# USB-Isolator_v10.net
KiCad netlist of a schematic drawn in EAGLE
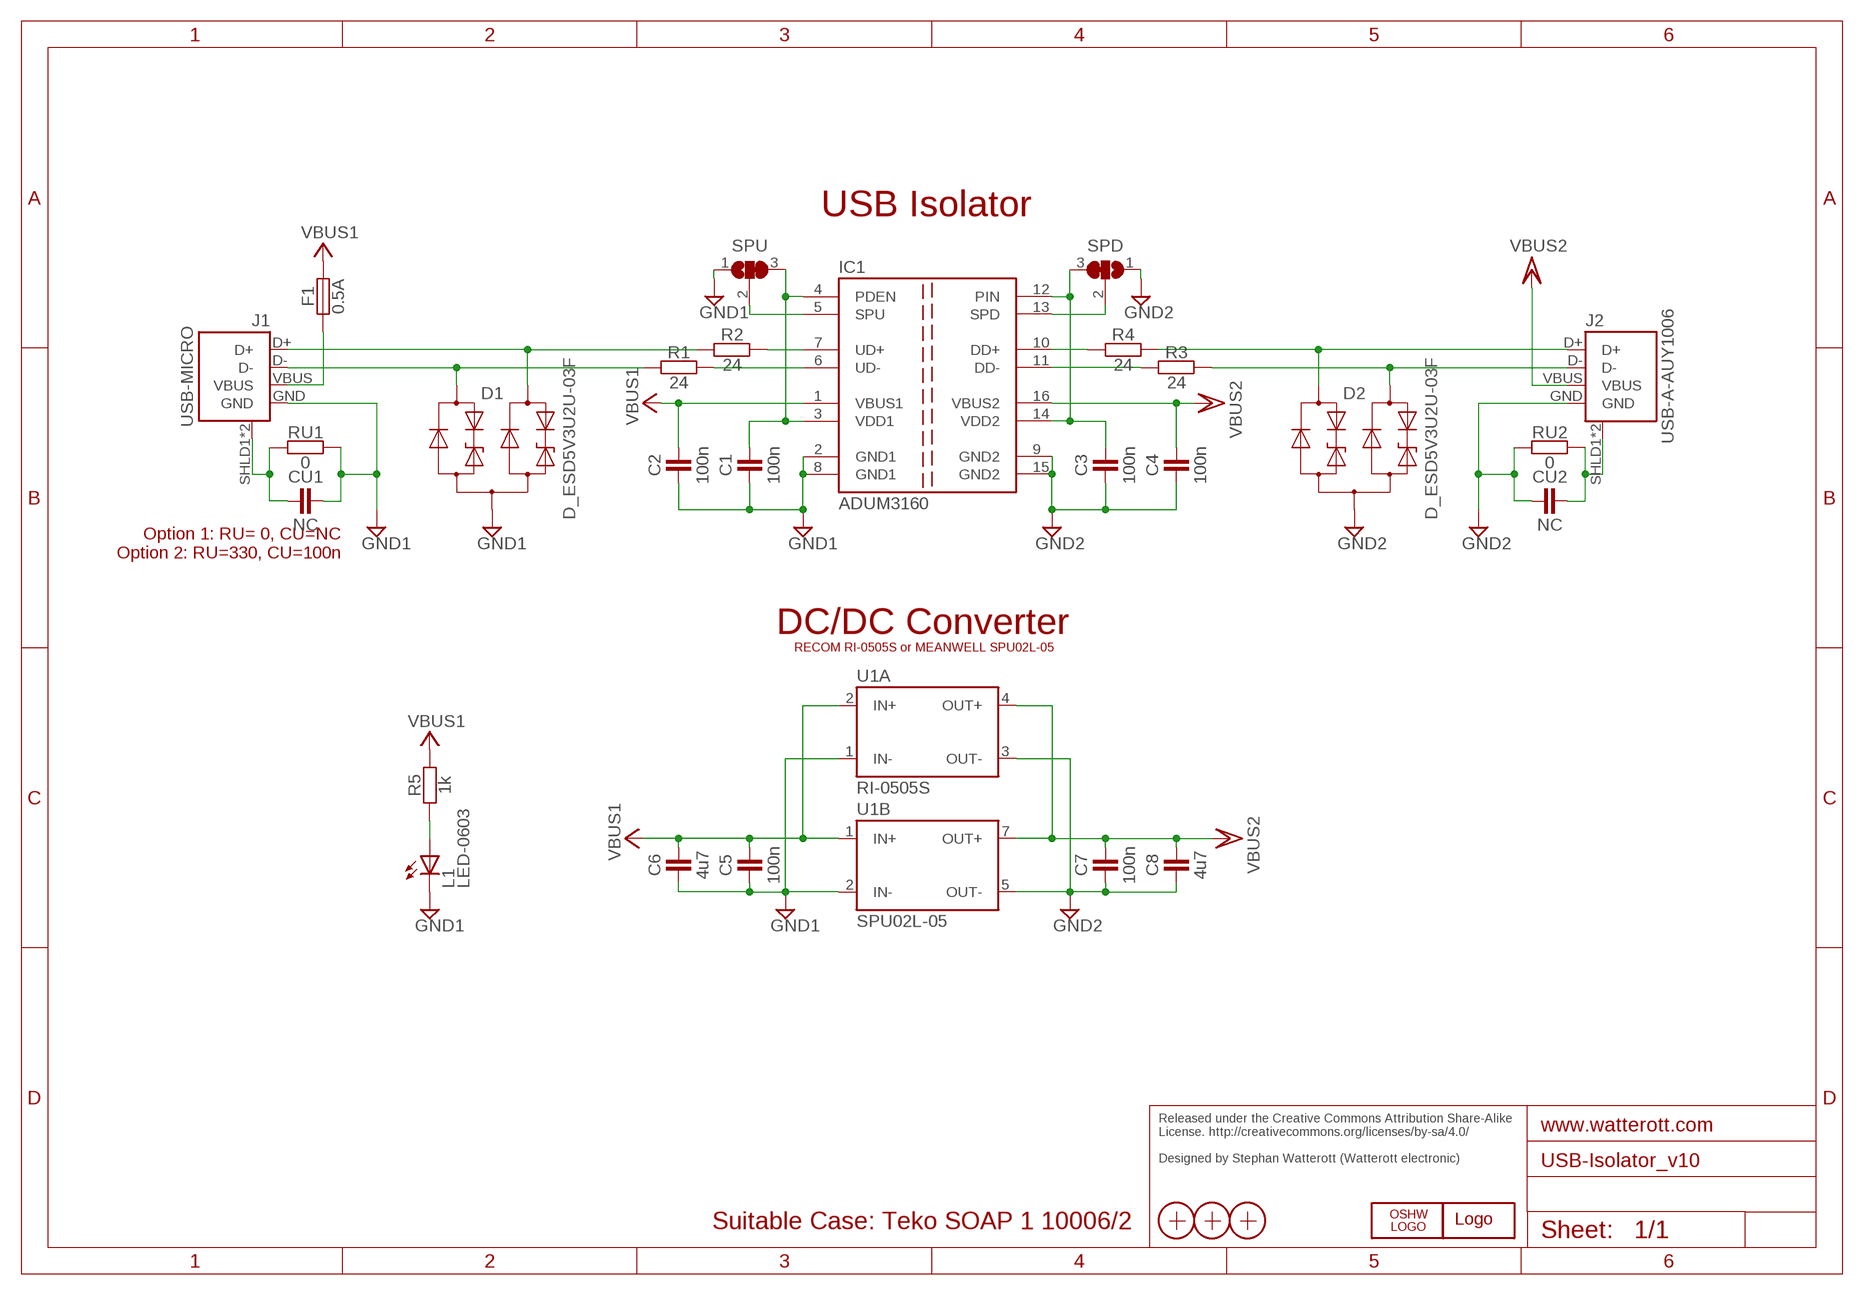
[diagram p0: schematic, sheet 1]

(export (version "E")
  (design (tool "Eeschema 10.0.6"))
  (components
    (comp (ref "C1")
      (value "100n")
      (footprint "eagle-import:R0603")
      (libsource (lib "eagle-import") (part "CAPACITOR-C0603"))
    )
    (comp (ref "C2")
      (value "100n")
      (footprint "eagle-import:R0603")
      (libsource (lib "eagle-import") (part "CAPACITOR-C0603"))
    )
    (comp (ref "C3")
      (value "100n")
      (footprint "eagle-import:R0603")
      (libsource (lib "eagle-import") (part "CAPACITOR-C0603"))
    )
    (comp (ref "C4")
      (value "100n")
      (footprint "eagle-import:R0603")
      (libsource (lib "eagle-import") (part "CAPACITOR-C0603"))
    )
    (comp (ref "C5")
      (value "100n")
      (footprint "eagle-import:R0603")
      (libsource (lib "eagle-import") (part "CAPACITOR-C0603"))
    )
    (comp (ref "C6")
      (value "4u7")
      (footprint "eagle-import:R1206")
      (libsource (lib "eagle-import") (part "CAPACITOR-C1206"))
    )
    (comp (ref "C7")
      (value "100n")
      (footprint "eagle-import:R0603")
      (libsource (lib "eagle-import") (part "CAPACITOR-C0603"))
    )
    (comp (ref "C8")
      (value "4u7")
      (footprint "eagle-import:R1206")
      (libsource (lib "eagle-import") (part "CAPACITOR-C1206"))
    )
    (comp (ref "CU1")
      (value "NC")
      (footprint "eagle-import:R0603")
      (libsource (lib "eagle-import") (part "CAPACITOR-C0603"))
    )
    (comp (ref "CU2")
      (value "NC")
      (footprint "eagle-import:R0603")
      (libsource (lib "eagle-import") (part "CAPACITOR-C0603"))
    )
    (comp (ref "D1")
      (value "D_ESD5V3U2U-03F")
      (footprint "eagle-import:TSFP3")
      (libsource (lib "eagle-import") (part "D_ESD5V3U2U-03F"))
    )
    (comp (ref "D2")
      (value "D_ESD5V3U2U-03F")
      (footprint "eagle-import:TSFP3")
      (libsource (lib "eagle-import") (part "D_ESD5V3U2U-03F"))
    )
    (comp (ref "F1")
      (value "0.5A")
      (footprint "eagle-import:R0805")
      (libsource (lib "eagle-import") (part "FUSE-0805"))
    )
    (comp (ref "IC1")
      (value "ADUM3160")
      (footprint "eagle-import:SO16W")
      (libsource (lib "eagle-import") (part "ADUM3160"))
    )
    (comp (ref "J1")
      (value "USB-MICRO")
      (footprint "eagle-import:USB-MICRO-10103594")
      (libsource (lib "eagle-import") (part "USB-MICRO"))
    )
    (comp (ref "J2")
      (value "USB-A-AUY1006")
      (footprint "eagle-import:USB-AU-Y1006-R")
      (fields (field (name "MANUFACTURER") "AU-Y1006-R"))
      (libsource (lib "eagle-import") (part "USB-A-AUY1006"))
    )
    (comp (ref "L1")
      (value "LED-0603")
      (footprint "eagle-import:LED_0603")
      (libsource (lib "eagle-import") (part "LED-0603"))
    )
    (comp (ref "LOGO2")
      (value "OSHW_LOGOX0070")
      (footprint "eagle-import:OSHW_6X70")
      (libsource (lib "eagle-import") (part "OSHW_LOGOX0070"))
    )
    (comp (ref "LOGO3")
      (value "LOGO-S_PLACE_M")
      (footprint "eagle-import:SPARK_TPLACE_M")
      (libsource (lib "eagle-import") (part "LOGO-S_PLACE_M"))
    )
    (comp (ref "R1")
      (value "24")
      (footprint "eagle-import:R0603")
      (libsource (lib "eagle-import") (part "RESISTOR-R0603"))
    )
    (comp (ref "R2")
      (value "24")
      (footprint "eagle-import:R0603")
      (libsource (lib "eagle-import") (part "RESISTOR-R0603"))
    )
    (comp (ref "R3")
      (value "24")
      (footprint "eagle-import:R0603")
      (libsource (lib "eagle-import") (part "RESISTOR-R0603"))
    )
    (comp (ref "R4")
      (value "24")
      (footprint "eagle-import:R0603")
      (libsource (lib "eagle-import") (part "RESISTOR-R0603"))
    )
    (comp (ref "R5")
      (value "1k")
      (footprint "eagle-import:R0603")
      (libsource (lib "eagle-import") (part "RESISTOR-R0603"))
    )
    (comp (ref "RU1")
      (value "0")
      (footprint "eagle-import:R0603")
      (libsource (lib "eagle-import") (part "RESISTOR-R0603"))
    )
    (comp (ref "RU2")
      (value "0")
      (footprint "eagle-import:R0603")
      (libsource (lib "eagle-import") (part "RESISTOR-R0603"))
    )
    (comp (ref "SPD")
      (value "JUMPER3")
      (footprint "eagle-import:JUMPER3")
      (libsource (lib "eagle-import") (part "JUMPER3"))
    )
    (comp (ref "SPU")
      (value "JUMPER3")
      (footprint "eagle-import:JUMPER3")
      (libsource (lib "eagle-import") (part "JUMPER3"))
    )
    (comp (ref "U1A")
      (value "RI-0505S")
      (footprint "eagle-import:RECOM_SIP4_RI")
      (libsource (lib "eagle-import") (part "DC/DC-RI"))
    )
    (comp (ref "U1B")
      (value "SPU02L-05")
      (footprint "eagle-import:MEANWELL_SIP7_SPU02")
      (libsource (lib "eagle-import") (part "DC/DC-SPU02"))
    )
    (comp (ref "X1")
      (value "PASSER-07")
      (footprint "eagle-import:PASSER_07MM")
      (libsource (lib "eagle-import") (part "PASSER-07"))
    )
    (comp (ref "X2")
      (value "PASSER-07")
      (footprint "eagle-import:PASSER_07MM")
      (libsource (lib "eagle-import") (part "PASSER-07"))
    )
    (comp (ref "X3")
      (value "PASSER-07")
      (footprint "eagle-import:PASSER_07MM")
      (libsource (lib "eagle-import") (part "PASSER-07"))
    )
  )
  (nets
    (net (code "1") (name "GND1") (class "Default")
      (node (ref "C1") (pin "1") (pinfunction "1_1") (pintype "passive"))
      (node (ref "C2") (pin "1") (pinfunction "1_1") (pintype "passive"))
      (node (ref "C5") (pin "1") (pinfunction "1_1") (pintype "passive"))
      (node (ref "C6") (pin "1") (pinfunction "1_1") (pintype "passive"))
      (node (ref "CU1") (pin "2") (pinfunction "2_2") (pintype "passive"))
      (node (ref "D1") (pin "3") (pinfunction "A_3") (pintype "passive"))
      (node (ref "IC1") (pin "2") (pinfunction "GND1_2") (pintype "power_in"))
      (node (ref "IC1") (pin "8") (pinfunction "GND1_8") (pintype "power_in"))
      (node (ref "J1") (pin "GND") (pinfunction "GND_GND") (pintype "power_in"))
      (node (ref "L1") (pin "C") (pinfunction "C_C") (pintype "passive"))
      (node (ref "RU1") (pin "2") (pinfunction "2_2") (pintype "passive"))
      (node (ref "SPU") (pin "1") (pinfunction "1_1") (pintype "passive"))
      (node (ref "U1A") (pin "1") (pinfunction "IN-_1") (pintype "power_in"))
      (node (ref "U1B") (pin "2") (pinfunction "IN-_2") (pintype "power_in"))
    )
    (net (code "2") (name "GND2") (class "Default")
      (node (ref "C3") (pin "1") (pinfunction "1_1") (pintype "passive"))
      (node (ref "C4") (pin "1") (pinfunction "1_1") (pintype "passive"))
      (node (ref "C7") (pin "1") (pinfunction "1_1") (pintype "passive"))
      (node (ref "C8") (pin "1") (pinfunction "1_1") (pintype "passive"))
      (node (ref "CU2") (pin "1") (pinfunction "1_1") (pintype "passive"))
      (node (ref "D2") (pin "3") (pinfunction "A_3") (pintype "passive"))
      (node (ref "IC1") (pin "15") (pinfunction "GND2_15") (pintype "power_in"))
      (node (ref "IC1") (pin "9") (pinfunction "GND2_9") (pintype "power_in"))
      (node (ref "J2") (pin "GND") (pinfunction "GND_GND") (pintype "power_in"))
      (node (ref "RU2") (pin "1") (pinfunction "1_1") (pintype "passive"))
      (node (ref "SPD") (pin "1") (pinfunction "1_1") (pintype "passive"))
      (node (ref "U1A") (pin "3") (pinfunction "OUT-_3") (pintype "power_in"))
      (node (ref "U1B") (pin "5") (pinfunction "OUT-_5") (pintype "power_in"))
    )
    (net (code "3") (name "Net-(CU1-Pad1)") (class "Default")
      (node (ref "CU1") (pin "1") (pinfunction "1_1") (pintype "passive"))
      (node (ref "J1") (pin "SHLD1") (pinfunction "SHIELD_SHLD1") (pintype "passive"))
      (node (ref "J1") (pin "SHLD2") (pinfunction "SHIELD_SHLD2") (pintype "passive"))
      (node (ref "RU1") (pin "1") (pinfunction "1_1") (pintype "passive"))
    )
    (net (code "4") (name "Net-(CU2-Pad2)") (class "Default")
      (node (ref "CU2") (pin "2") (pinfunction "2_2") (pintype "passive"))
      (node (ref "J2") (pin "SHLD1") (pinfunction "SHIELD_SHLD1") (pintype "passive"))
      (node (ref "J2") (pin "SHLD2") (pinfunction "SHIELD_SHLD2") (pintype "passive"))
      (node (ref "RU2") (pin "2") (pinfunction "2_2") (pintype "passive"))
    )
    (net (code "5") (name "Net-(D1-C1)") (class "Default")
      (node (ref "D1") (pin "1") (pinfunction "C1_1") (pintype "passive"))
      (node (ref "J1") (pin "D-") (pinfunction "D-_D-") (pintype "bidirectional"))
      (node (ref "R1") (pin "1") (pinfunction "1_1") (pintype "passive"))
    )
    (net (code "6") (name "Net-(D1-C2)") (class "Default")
      (node (ref "D1") (pin "2") (pinfunction "C2_2") (pintype "passive"))
      (node (ref "J1") (pin "D+") (pinfunction "D+_D+") (pintype "bidirectional"))
      (node (ref "R2") (pin "1") (pinfunction "1_1") (pintype "passive"))
    )
    (net (code "7") (name "Net-(D2-C1)") (class "Default")
      (node (ref "D2") (pin "1") (pinfunction "C1_1") (pintype "passive"))
      (node (ref "J2") (pin "D+") (pinfunction "D+_D+") (pintype "bidirectional"))
      (node (ref "R4") (pin "2") (pinfunction "2_2") (pintype "passive"))
    )
    (net (code "8") (name "Net-(D2-C2)") (class "Default")
      (node (ref "D2") (pin "2") (pinfunction "C2_2") (pintype "passive"))
      (node (ref "J2") (pin "D-") (pinfunction "D-_D-") (pintype "bidirectional"))
      (node (ref "R3") (pin "2") (pinfunction "2_2") (pintype "passive"))
    )
    (net (code "9") (name "Net-(F1-Pad1)") (class "Default")
      (node (ref "F1") (pin "1") (pinfunction "1_1") (pintype "passive"))
      (node (ref "J1") (pin "VBUS") (pinfunction "VBUS_VBUS") (pintype "power_in"))
    )
    (net (code "10") (name "Net-(IC1-DD+)") (class "Default")
      (node (ref "IC1") (pin "10") (pinfunction "DD+_10") (pintype "bidirectional"))
      (node (ref "R4") (pin "1") (pinfunction "1_1") (pintype "passive"))
    )
    (net (code "11") (name "Net-(IC1-DD-)") (class "Default")
      (node (ref "IC1") (pin "11") (pinfunction "DD-_11") (pintype "bidirectional"))
      (node (ref "R3") (pin "1") (pinfunction "1_1") (pintype "passive"))
    )
    (net (code "12") (name "Net-(IC1-PDEN)") (class "Default")
      (node (ref "C1") (pin "2") (pinfunction "2_2") (pintype "passive"))
      (node (ref "IC1") (pin "3") (pinfunction "VDD1_3") (pintype "power_in"))
      (node (ref "IC1") (pin "4") (pinfunction "PDEN_4") (pintype "input"))
      (node (ref "SPU") (pin "3") (pinfunction "3_3") (pintype "passive"))
    )
    (net (code "13") (name "Net-(IC1-PIN)") (class "Default")
      (node (ref "C3") (pin "2") (pinfunction "2_2") (pintype "passive"))
      (node (ref "IC1") (pin "12") (pinfunction "PIN_12") (pintype "input"))
      (node (ref "IC1") (pin "14") (pinfunction "VDD2_14") (pintype "power_in"))
      (node (ref "SPD") (pin "3") (pinfunction "3_3") (pintype "passive"))
    )
    (net (code "14") (name "Net-(IC1-SPD)") (class "Default")
      (node (ref "IC1") (pin "13") (pinfunction "SPD_13") (pintype "input"))
      (node (ref "SPD") (pin "2") (pinfunction "2_2") (pintype "passive"))
    )
    (net (code "15") (name "Net-(IC1-SPU)") (class "Default")
      (node (ref "IC1") (pin "5") (pinfunction "SPU_5") (pintype "input"))
      (node (ref "SPU") (pin "2") (pinfunction "2_2") (pintype "passive"))
    )
    (net (code "16") (name "Net-(IC1-UD+)") (class "Default")
      (node (ref "IC1") (pin "7") (pinfunction "UD+_7") (pintype "bidirectional"))
      (node (ref "R2") (pin "2") (pinfunction "2_2") (pintype "passive"))
    )
    (net (code "17") (name "Net-(IC1-UD-)") (class "Default")
      (node (ref "IC1") (pin "6") (pinfunction "UD-_6") (pintype "bidirectional"))
      (node (ref "R1") (pin "2") (pinfunction "2_2") (pintype "passive"))
    )
    (net (code "18") (name "Net-(L1-PadA)") (class "Default")
      (node (ref "L1") (pin "A") (pinfunction "A_A") (pintype "passive"))
      (node (ref "R5") (pin "1") (pinfunction "1_1") (pintype "passive"))
    )
    (net (code "19") (name "VBUS1") (class "Default")
      (node (ref "C2") (pin "2") (pinfunction "2_2") (pintype "passive"))
      (node (ref "C5") (pin "2") (pinfunction "2_2") (pintype "passive"))
      (node (ref "C6") (pin "2") (pinfunction "2_2") (pintype "passive"))
      (node (ref "F1") (pin "2") (pinfunction "2_2") (pintype "passive"))
      (node (ref "IC1") (pin "1") (pinfunction "VBUS1_1") (pintype "power_in"))
      (node (ref "R5") (pin "2") (pinfunction "2_2") (pintype "passive"))
      (node (ref "U1A") (pin "2") (pinfunction "IN+_2") (pintype "power_in"))
      (node (ref "U1B") (pin "1") (pinfunction "IN+_1") (pintype "power_in"))
    )
    (net (code "20") (name "VBUS2") (class "Default")
      (node (ref "C4") (pin "2") (pinfunction "2_2") (pintype "passive"))
      (node (ref "C7") (pin "2") (pinfunction "2_2") (pintype "passive"))
      (node (ref "C8") (pin "2") (pinfunction "2_2") (pintype "passive"))
      (node (ref "IC1") (pin "16") (pinfunction "VBUS2_16") (pintype "power_in"))
      (node (ref "J2") (pin "VBUS") (pinfunction "VBUS_VBUS") (pintype "power_in"))
      (node (ref "U1A") (pin "4") (pinfunction "OUT+_4") (pintype "power_in"))
      (node (ref "U1B") (pin "7") (pinfunction "OUT+_7") (pintype "power_in"))
    )
  )
)
